# Sensor_Module_0xXX_Prototyping_v1.net
KiCad netlist of a schematic drawn in EAGLE
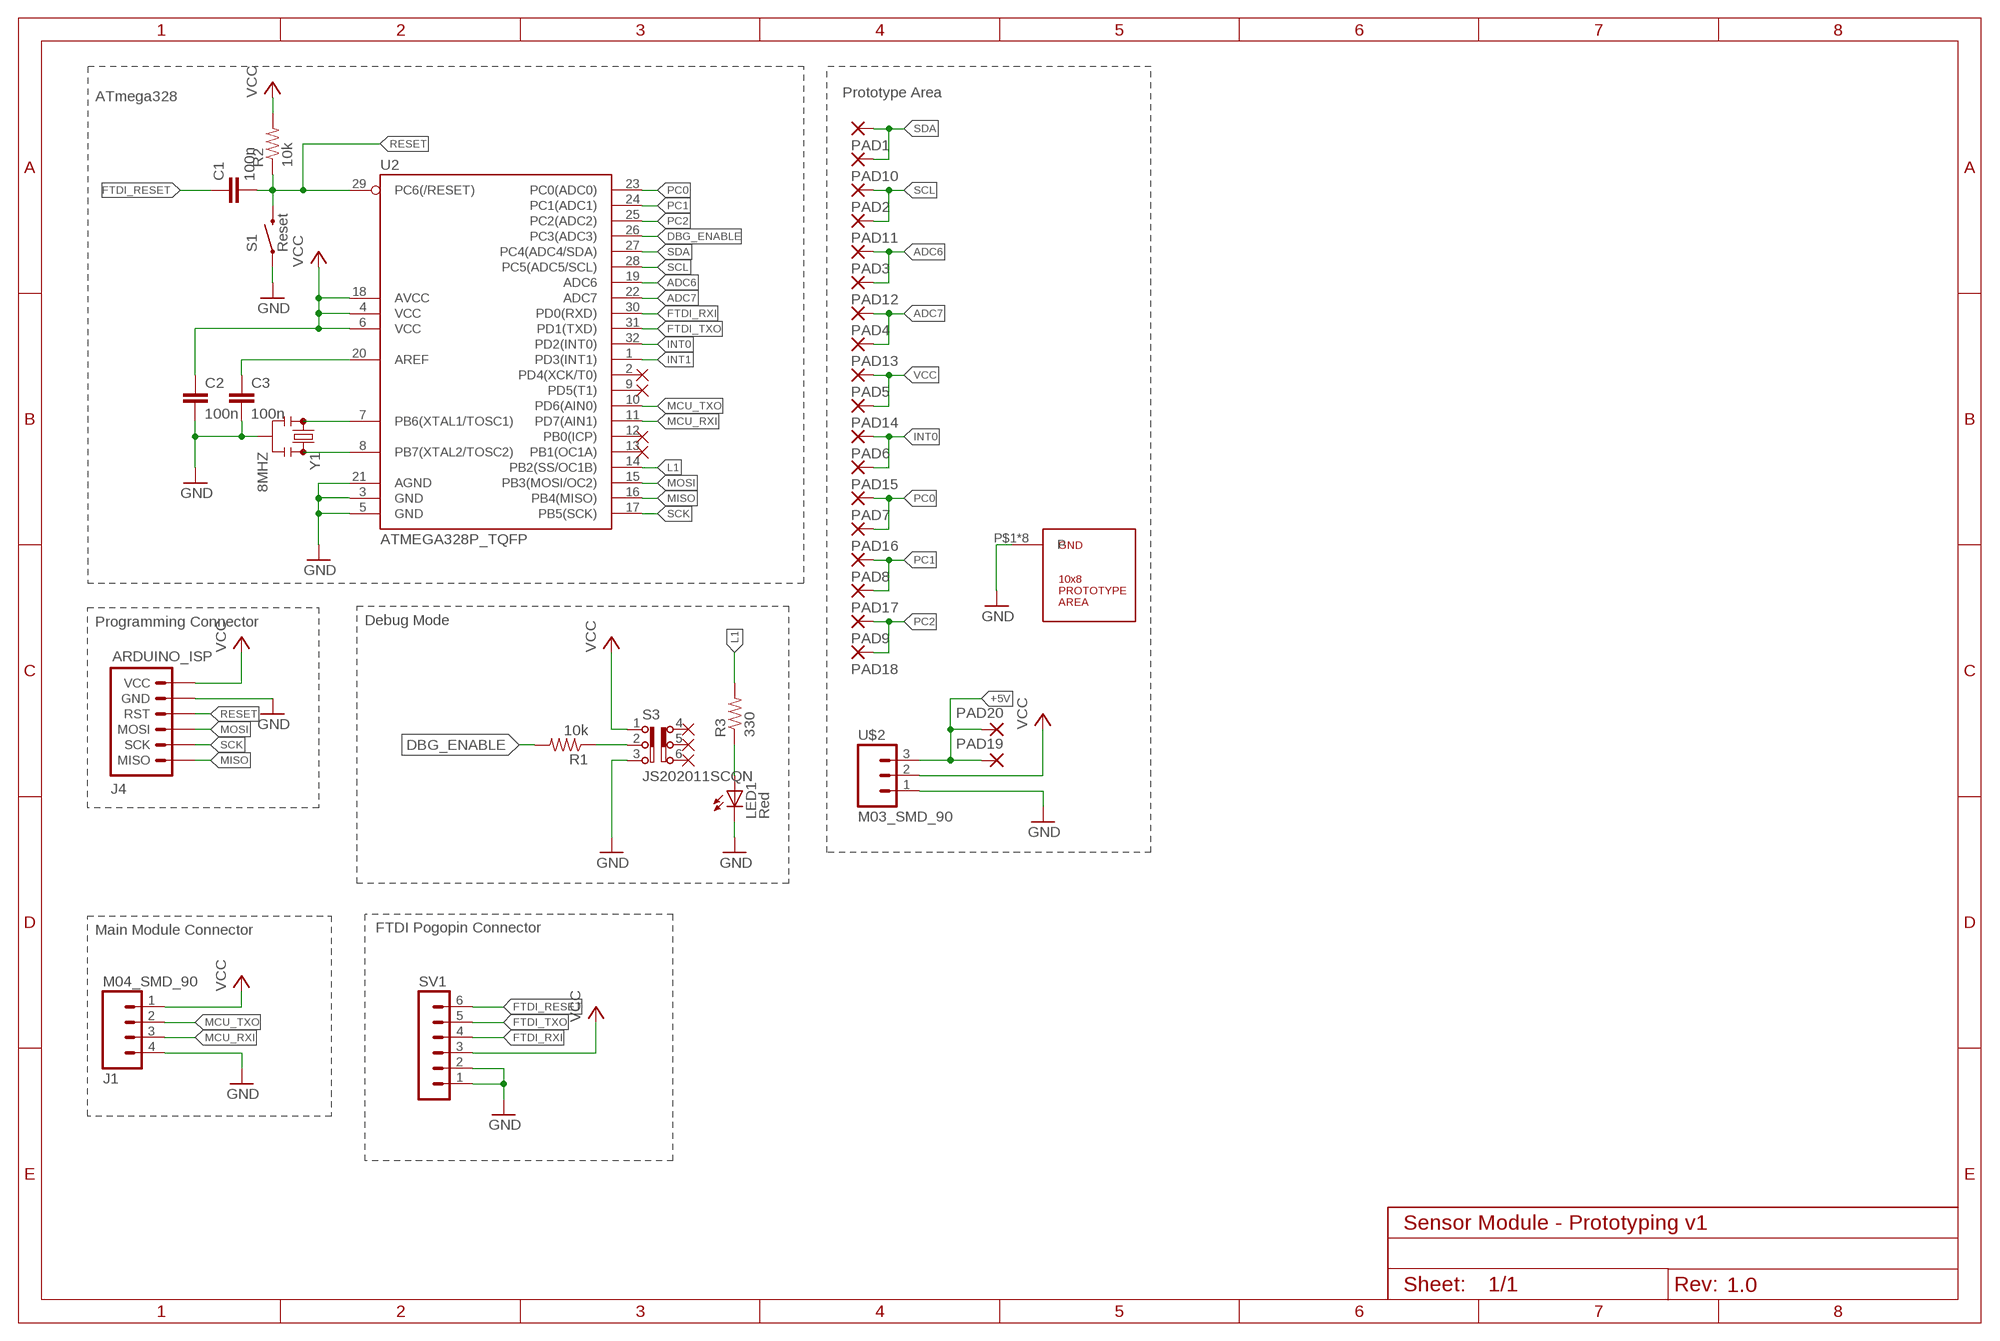
[diagram p0: schematic, sheet 1]

(export (version "E")
  (design (tool "Eeschema 10.0.6"))
  (components
    (comp (ref "C1")
      (value "100n")
      (footprint "eagle-import:C0805")
      (libsource (lib "eagle-import") (part "C"))
    )
    (comp (ref "C2")
      (value "100n")
      (footprint "eagle-import:C0805")
      (libsource (lib "eagle-import") (part "C"))
    )
    (comp (ref "C3")
      (value "100n")
      (footprint "eagle-import:C0805")
      (libsource (lib "eagle-import") (part "C"))
    )
    (comp (ref "J1")
      (value "M04_SMD_90")
      (footprint "eagle-import:M04_SMD_90")
      (libsource (lib "eagle-import") (part "M04_SMD_90"))
    )
    (comp (ref "J4")
      (value "ARDUINO_ISP")
      (footprint "eagle-import:M-2X3")
      (libsource (lib "eagle-import") (part "ARDUINO_ISP"))
    )
    (comp (ref "LED1")
      (value "Red")
      (footprint "eagle-import:SML0805")
      (libsource (lib "eagle-import") (part "LEDSML0805"))
    )
    (comp (ref "PAD1")
      (value "1,6/0,9")
      (footprint "eagle-import:1,6_0,9")
      (libsource (lib "eagle-import") (part "1,6/0,9"))
    )
    (comp (ref "PAD2")
      (value "1,6/0,9")
      (footprint "eagle-import:1,6_0,9")
      (libsource (lib "eagle-import") (part "1,6/0,9"))
    )
    (comp (ref "PAD3")
      (value "1,6/0,9")
      (footprint "eagle-import:1,6_0,9")
      (libsource (lib "eagle-import") (part "1,6/0,9"))
    )
    (comp (ref "PAD4")
      (value "1,6/0,9")
      (footprint "eagle-import:1,6_0,9")
      (libsource (lib "eagle-import") (part "1,6/0,9"))
    )
    (comp (ref "PAD5")
      (value "1,6/0,9")
      (footprint "eagle-import:1,6_0,9")
      (libsource (lib "eagle-import") (part "1,6/0,9"))
    )
    (comp (ref "PAD6")
      (value "1,6/0,9")
      (footprint "eagle-import:1,6_0,9")
      (libsource (lib "eagle-import") (part "1,6/0,9"))
    )
    (comp (ref "PAD7")
      (value "1,6/0,9")
      (footprint "eagle-import:1,6_0,9")
      (libsource (lib "eagle-import") (part "1,6/0,9"))
    )
    (comp (ref "PAD8")
      (value "1,6/0,9")
      (footprint "eagle-import:1,6_0,9")
      (libsource (lib "eagle-import") (part "1,6/0,9"))
    )
    (comp (ref "PAD9")
      (value "1,6/0,9")
      (footprint "eagle-import:1,6_0,9")
      (libsource (lib "eagle-import") (part "1,6/0,9"))
    )
    (comp (ref "PAD10")
      (value "1,6/0,9")
      (footprint "eagle-import:1,6_0,9")
      (libsource (lib "eagle-import") (part "1,6/0,9"))
    )
    (comp (ref "PAD11")
      (value "1,6/0,9")
      (footprint "eagle-import:1,6_0,9")
      (libsource (lib "eagle-import") (part "1,6/0,9"))
    )
    (comp (ref "PAD12")
      (value "1,6/0,9")
      (footprint "eagle-import:1,6_0,9")
      (libsource (lib "eagle-import") (part "1,6/0,9"))
    )
    (comp (ref "PAD13")
      (value "1,6/0,9")
      (footprint "eagle-import:1,6_0,9")
      (libsource (lib "eagle-import") (part "1,6/0,9"))
    )
    (comp (ref "PAD14")
      (value "1,6/0,9")
      (footprint "eagle-import:1,6_0,9")
      (libsource (lib "eagle-import") (part "1,6/0,9"))
    )
    (comp (ref "PAD15")
      (value "1,6/0,9")
      (footprint "eagle-import:1,6_0,9")
      (libsource (lib "eagle-import") (part "1,6/0,9"))
    )
    (comp (ref "PAD16")
      (value "1,6/0,9")
      (footprint "eagle-import:1,6_0,9")
      (libsource (lib "eagle-import") (part "1,6/0,9"))
    )
    (comp (ref "PAD17")
      (value "1,6/0,9")
      (footprint "eagle-import:1,6_0,9")
      (libsource (lib "eagle-import") (part "1,6/0,9"))
    )
    (comp (ref "PAD18")
      (value "1,6/0,9")
      (footprint "eagle-import:1,6_0,9")
      (libsource (lib "eagle-import") (part "1,6/0,9"))
    )
    (comp (ref "PAD19")
      (value "1,6/0,9")
      (footprint "eagle-import:1,6_0,9")
      (libsource (lib "eagle-import") (part "1,6/0,9"))
    )
    (comp (ref "PAD20")
      (value "1,6/0,9")
      (footprint "eagle-import:1,6_0,9")
      (libsource (lib "eagle-import") (part "1,6/0,9"))
    )
    (comp (ref "R1")
      (value "10k")
      (footprint "eagle-import:0805")
      (libsource (lib "eagle-import") (part "RESISTOR0805-RES"))
    )
    (comp (ref "R2")
      (value "10k")
      (footprint "eagle-import:0805")
      (libsource (lib "eagle-import") (part "RESISTOR0805-RES"))
    )
    (comp (ref "R3")
      (value "330")
      (footprint "eagle-import:0805")
      (libsource (lib "eagle-import") (part "RESISTOR0805-RES"))
    )
    (comp (ref "S1")
      (value "Reset")
      (footprint "eagle-import:M-PUSHBUTTON-SMD")
      (libsource (lib "eagle-import") (part "PUSHBUTTON"))
    )
    (comp (ref "S3")
      (value "JS202011SCQN")
      (footprint "eagle-import:JS202011SCQN")
      (libsource (lib "eagle-import") (part "JS202011SCQN"))
    )
    (comp (ref "SV1")
      (value "MA06-1")
      (footprint "eagle-import:MA06-1")
      (libsource (lib "eagle-import") (part "MA06-1"))
    )
    (comp (ref "U$1")
      (value "10X8_PROTOTYPE_AREA")
      (footprint "eagle-import:10X8_PROTOTYPE_AREA")
      (libsource (lib "eagle-import") (part "10X8_PROTOTYPE_AREA"))
    )
    (comp (ref "U$2")
      (value "M03_SMD_90")
      (footprint "eagle-import:M03_SMD_90")
      (libsource (lib "eagle-import") (part "M03_SMD_90"))
    )
    (comp (ref "U2")
      (value "ATMEGA328P_TQFP")
      (footprint "eagle-import:TQFP32-08")
      (libsource (lib "eagle-import") (part "ATMEGA328P_TQFP"))
    )
    (comp (ref "Y1")
      (value "8MHZ")
      (footprint "eagle-import:RESONATOR-SMD")
      (libsource (lib "eagle-import") (part "RESONATOR8MHZ"))
    )
  )
  (nets
    (net (code "1") (name "+5V") (class "Default")
      (node (ref "PAD19") (pin "1") (pinfunction "P_1") (pintype "passive"))
      (node (ref "PAD20") (pin "1") (pinfunction "P_1") (pintype "passive"))
      (node (ref "U$2") (pin "3") (pinfunction "3_3") (pintype "passive"))
    )
    (net (code "2") (name "ADC6") (class "Default")
      (node (ref "PAD12") (pin "1") (pinfunction "P_1") (pintype "passive"))
      (node (ref "PAD3") (pin "1") (pinfunction "P_1") (pintype "passive"))
      (node (ref "U2") (pin "19") (pinfunction "ADC6_19") (pintype "bidirectional"))
    )
    (net (code "3") (name "ADC7") (class "Default")
      (node (ref "PAD13") (pin "1") (pinfunction "P_1") (pintype "passive"))
      (node (ref "PAD4") (pin "1") (pinfunction "P_1") (pintype "passive"))
      (node (ref "U2") (pin "22") (pinfunction "ADC7_22") (pintype "bidirectional"))
    )
    (net (code "4") (name "DBG_ENABLE") (class "Default")
      (node (ref "R1") (pin "2") (pinfunction "2_2") (pintype "passive"))
      (node (ref "U2") (pin "26") (pinfunction "PC3(ADC3)_26") (pintype "bidirectional"))
    )
    (net (code "5") (name "FTDI_RESET") (class "Default")
      (node (ref "C1") (pin "1") (pinfunction "1_1") (pintype "passive"))
      (node (ref "SV1") (pin "6") (pinfunction "6_6") (pintype "passive"))
    )
    (net (code "6") (name "FTDI_RXI") (class "Default")
      (node (ref "SV1") (pin "4") (pinfunction "4_4") (pintype "passive"))
      (node (ref "U2") (pin "30") (pinfunction "PD0(RXD)_30") (pintype "bidirectional"))
    )
    (net (code "7") (name "FTDI_TXO") (class "Default")
      (node (ref "SV1") (pin "5") (pinfunction "5_5") (pintype "passive"))
      (node (ref "U2") (pin "31") (pinfunction "PD1(TXD)_31") (pintype "bidirectional"))
    )
    (net (code "8") (name "GND") (class "Default")
      (node (ref "C2") (pin "2") (pinfunction "2_2") (pintype "passive"))
      (node (ref "C3") (pin "2") (pinfunction "2_2") (pintype "passive"))
      (node (ref "J1") (pin "4") (pinfunction "4_4") (pintype "passive"))
      (node (ref "J4") (pin "P$5") (pinfunction "GND_P$5") (pintype "passive"))
      (node (ref "LED1") (pin "C") (pinfunction "C_C") (pintype "passive"))
      (node (ref "S1") (pin "1") (pinfunction "LEFT_1") (pintype "passive"))
      (node (ref "S1") (pin "2") (pinfunction "LEFT_2") (pintype "passive"))
      (node (ref "S3") (pin "3") (pinfunction "3_3") (pintype "passive"))
      (node (ref "SV1") (pin "1") (pinfunction "1_1") (pintype "passive"))
      (node (ref "SV1") (pin "2") (pinfunction "2_2") (pintype "passive"))
      (node (ref "U$1") (pin "P$1") (pinfunction "P_P$1") (pintype "bidirectional"))
      (node (ref "U$1") (pin "P$2") (pinfunction "P_P$2") (pintype "bidirectional"))
      (node (ref "U$1") (pin "P$3") (pinfunction "P_P$3") (pintype "bidirectional"))
      (node (ref "U$1") (pin "P$4") (pinfunction "P_P$4") (pintype "bidirectional"))
      (node (ref "U$1") (pin "P$5") (pinfunction "P_P$5") (pintype "bidirectional"))
      (node (ref "U$1") (pin "P$6") (pinfunction "P_P$6") (pintype "bidirectional"))
      (node (ref "U$1") (pin "P$7") (pinfunction "P_P$7") (pintype "bidirectional"))
      (node (ref "U$1") (pin "P$8") (pinfunction "P_P$8") (pintype "bidirectional"))
      (node (ref "U$2") (pin "1") (pinfunction "1_1") (pintype "passive"))
      (node (ref "U2") (pin "21") (pinfunction "AGND_21") (pintype "bidirectional"))
      (node (ref "U2") (pin "3") (pinfunction "GND_3") (pintype "bidirectional"))
      (node (ref "U2") (pin "5") (pinfunction "GND_5") (pintype "bidirectional"))
      (node (ref "Y1") (pin "2") (pinfunction "2_2") (pintype "passive"))
    )
    (net (code "9") (name "INT0") (class "Default")
      (node (ref "PAD15") (pin "1") (pinfunction "P_1") (pintype "passive"))
      (node (ref "PAD6") (pin "1") (pinfunction "P_1") (pintype "passive"))
      (node (ref "U2") (pin "32") (pinfunction "PD2(INT0)_32") (pintype "bidirectional"))
    )
    (net (code "10") (name "INT1") (class "Default")
      (node (ref "U2") (pin "1") (pinfunction "PD3(INT1)_1") (pintype "bidirectional"))
    )
    (net (code "11") (name "L1") (class "Default")
      (node (ref "R3") (pin "2") (pinfunction "2_2") (pintype "passive"))
      (node (ref "U2") (pin "14") (pinfunction "PB2(SS/OC1B)_14") (pintype "bidirectional"))
    )
    (net (code "12") (name "MCU_RXI") (class "Default")
      (node (ref "J1") (pin "3") (pinfunction "3_3") (pintype "passive"))
      (node (ref "U2") (pin "11") (pinfunction "PD7(AIN1)_11") (pintype "bidirectional"))
    )
    (net (code "13") (name "MCU_TXO") (class "Default")
      (node (ref "J1") (pin "2") (pinfunction "2_2") (pintype "passive"))
      (node (ref "U2") (pin "10") (pinfunction "PD6(AIN0)_10") (pintype "bidirectional"))
    )
    (net (code "14") (name "MISO") (class "Default")
      (node (ref "J4") (pin "P$1") (pinfunction "MISO_P$1") (pintype "passive"))
      (node (ref "U2") (pin "16") (pinfunction "PB4(MISO)_16") (pintype "bidirectional"))
    )
    (net (code "15") (name "MOSI") (class "Default")
      (node (ref "J4") (pin "P$3") (pinfunction "MOSI_P$3") (pintype "passive"))
      (node (ref "U2") (pin "15") (pinfunction "PB3(MOSI/OC2)_15") (pintype "bidirectional"))
    )
    (net (code "16") (name "Net-(LED1-PadA)") (class "Default")
      (node (ref "LED1") (pin "A") (pinfunction "A_A") (pintype "passive"))
      (node (ref "R3") (pin "1") (pinfunction "1_1") (pintype "passive"))
    )
    (net (code "17") (name "Net-(R1-Pad1)") (class "Default")
      (node (ref "R1") (pin "1") (pinfunction "1_1") (pintype "passive"))
      (node (ref "S3") (pin "2") (pinfunction "2_2") (pintype "passive"))
    )
    (net (code "18") (name "Net-(U2-AREF)") (class "Default")
      (node (ref "C3") (pin "1") (pinfunction "1_1") (pintype "passive"))
      (node (ref "U2") (pin "20") (pinfunction "AREF_20") (pintype "bidirectional"))
    )
    (net (code "19") (name "Net-(U2-PB6(XTAL1{slash}TOSC1))") (class "Default")
      (node (ref "U2") (pin "7") (pinfunction "PB6(XTAL1/TOSC1)_7") (pintype "bidirectional"))
      (node (ref "Y1") (pin "1") (pinfunction "1_1") (pintype "passive"))
    )
    (net (code "20") (name "Net-(U2-PB7(XTAL2{slash}TOSC2))") (class "Default")
      (node (ref "U2") (pin "8") (pinfunction "PB7(XTAL2/TOSC2)_8") (pintype "bidirectional"))
      (node (ref "Y1") (pin "3") (pinfunction "3_3") (pintype "passive"))
    )
    (net (code "21") (name "PC0") (class "Default")
      (node (ref "PAD16") (pin "1") (pinfunction "P_1") (pintype "passive"))
      (node (ref "PAD7") (pin "1") (pinfunction "P_1") (pintype "passive"))
      (node (ref "U2") (pin "23") (pinfunction "PC0(ADC0)_23") (pintype "bidirectional"))
    )
    (net (code "22") (name "PC1") (class "Default")
      (node (ref "PAD17") (pin "1") (pinfunction "P_1") (pintype "passive"))
      (node (ref "PAD8") (pin "1") (pinfunction "P_1") (pintype "passive"))
      (node (ref "U2") (pin "24") (pinfunction "PC1(ADC1)_24") (pintype "bidirectional"))
    )
    (net (code "23") (name "PC2") (class "Default")
      (node (ref "PAD18") (pin "1") (pinfunction "P_1") (pintype "passive"))
      (node (ref "PAD9") (pin "1") (pinfunction "P_1") (pintype "passive"))
      (node (ref "U2") (pin "25") (pinfunction "PC2(ADC2)_25") (pintype "bidirectional"))
    )
    (net (code "24") (name "RESET") (class "Default")
      (node (ref "C1") (pin "2") (pinfunction "2_2") (pintype "passive"))
      (node (ref "J4") (pin "P$4") (pinfunction "RST_P$4") (pintype "passive"))
      (node (ref "R2") (pin "1") (pinfunction "1_1") (pintype "passive"))
      (node (ref "S1") (pin "3") (pinfunction "RIGHT_3") (pintype "passive"))
      (node (ref "S1") (pin "4") (pinfunction "RIGHT_4") (pintype "passive"))
      (node (ref "U2") (pin "29") (pinfunction "PC6(/RESET)_29") (pintype "bidirectional"))
    )
    (net (code "25") (name "SCK") (class "Default")
      (node (ref "J4") (pin "P$2") (pinfunction "SCK_P$2") (pintype "passive"))
      (node (ref "U2") (pin "17") (pinfunction "PB5(SCK)_17") (pintype "bidirectional"))
    )
    (net (code "26") (name "SCL") (class "Default")
      (node (ref "PAD11") (pin "1") (pinfunction "P_1") (pintype "passive"))
      (node (ref "PAD2") (pin "1") (pinfunction "P_1") (pintype "passive"))
      (node (ref "U2") (pin "28") (pinfunction "PC5(ADC5/SCL)_28") (pintype "bidirectional"))
    )
    (net (code "27") (name "SDA") (class "Default")
      (node (ref "PAD1") (pin "1") (pinfunction "P_1") (pintype "passive"))
      (node (ref "PAD10") (pin "1") (pinfunction "P_1") (pintype "passive"))
      (node (ref "U2") (pin "27") (pinfunction "PC4(ADC4/SDA)_27") (pintype "bidirectional"))
    )
    (net (code "28") (name "VCC") (class "Default")
      (node (ref "C2") (pin "1") (pinfunction "1_1") (pintype "passive"))
      (node (ref "J1") (pin "1") (pinfunction "1_1") (pintype "passive"))
      (node (ref "J4") (pin "P$6") (pinfunction "VCC_P$6") (pintype "passive"))
      (node (ref "PAD14") (pin "1") (pinfunction "P_1") (pintype "passive"))
      (node (ref "PAD5") (pin "1") (pinfunction "P_1") (pintype "passive"))
      (node (ref "R2") (pin "2") (pinfunction "2_2") (pintype "passive"))
      (node (ref "S3") (pin "1") (pinfunction "1_1") (pintype "passive"))
      (node (ref "SV1") (pin "3") (pinfunction "3_3") (pintype "passive"))
      (node (ref "U$2") (pin "2") (pinfunction "2_2") (pintype "passive"))
      (node (ref "U2") (pin "18") (pinfunction "AVCC_18") (pintype "bidirectional"))
      (node (ref "U2") (pin "4") (pinfunction "VCC_4") (pintype "bidirectional"))
      (node (ref "U2") (pin "6") (pinfunction "VCC_6") (pintype "bidirectional"))
    )
    (net (code "29") (name "unconnected-(S3-Pad4)") (class "Default")
      (node (ref "S3") (pin "4") (pinfunction "4_4") (pintype "passive"))
    )
    (net (code "30") (name "unconnected-(S3-Pad5)") (class "Default")
      (node (ref "S3") (pin "5") (pinfunction "5_5") (pintype "passive"))
    )
    (net (code "31") (name "unconnected-(S3-Pad6)") (class "Default")
      (node (ref "S3") (pin "6") (pinfunction "6_6") (pintype "passive"))
    )
    (net (code "32") (name "unconnected-(U2-PB0(ICP)-Pad12)") (class "Default")
      (node (ref "U2") (pin "12") (pinfunction "PB0(ICP)_12") (pintype "bidirectional"))
    )
    (net (code "33") (name "unconnected-(U2-PB1(OC1A)-Pad13)") (class "Default")
      (node (ref "U2") (pin "13") (pinfunction "PB1(OC1A)_13") (pintype "bidirectional"))
    )
    (net (code "34") (name "unconnected-(U2-PD4(XCK{slash}T0)-Pad2)") (class "Default")
      (node (ref "U2") (pin "2") (pinfunction "PD4(XCK/T0)_2") (pintype "bidirectional"))
    )
    (net (code "35") (name "unconnected-(U2-PD5(T1)-Pad9)") (class "Default")
      (node (ref "U2") (pin "9") (pinfunction "PD5(T1)_9") (pintype "bidirectional"))
    )
  )
)
